# transmitter_new.net
KiCad netlist of a schematic drawn in EAGLE
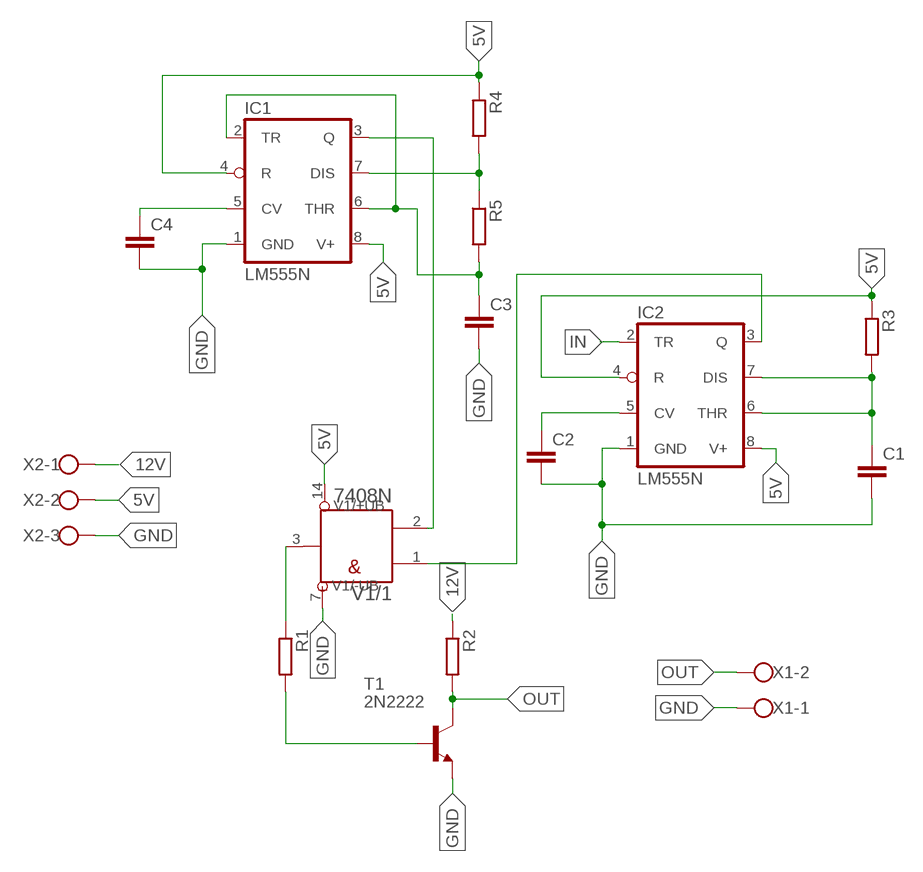
[diagram p0: schematic, sheet 1]

(export (version "E")
  (design (tool "Eeschema 10.0.6"))
  (components
    (comp (ref "C1")
      (value "C-EU050-025X075")
      (footprint "eagle-import:C050-025X075")
      (libsource (lib "eagle-import") (part "C-EU050-025X075"))
    )
    (comp (ref "C2")
      (value "C-EU050-025X075")
      (footprint "eagle-import:C050-025X075")
      (libsource (lib "eagle-import") (part "C-EU050-025X075"))
    )
    (comp (ref "C3")
      (value "C-EU050-025X075")
      (footprint "eagle-import:C050-025X075")
      (libsource (lib "eagle-import") (part "C-EU050-025X075"))
    )
    (comp (ref "C4")
      (value "C-EU050-025X075")
      (footprint "eagle-import:C050-025X075")
      (libsource (lib "eagle-import") (part "C-EU050-025X075"))
    )
    (comp (ref "IC1")
      (value "LM555N")
      (footprint "eagle-import:DIL08")
      (libsource (lib "eagle-import") (part "555NLM"))
    )
    (comp (ref "IC2")
      (value "LM555N")
      (footprint "eagle-import:DIL08")
      (libsource (lib "eagle-import") (part "555NLM"))
    )
    (comp (ref "R1")
      (value "R-EU_0207/10")
      (footprint "eagle-import:0207_10")
      (libsource (lib "eagle-import") (part "R-EU_0207/10"))
    )
    (comp (ref "R2")
      (value "R-EU_0207/10")
      (footprint "eagle-import:0207_10")
      (libsource (lib "eagle-import") (part "R-EU_0207/10"))
    )
    (comp (ref "R3")
      (value "R-EU_0207/10")
      (footprint "eagle-import:0207_10")
      (libsource (lib "eagle-import") (part "R-EU_0207/10"))
    )
    (comp (ref "R4")
      (value "R-EU_0207/10")
      (footprint "eagle-import:0207_10")
      (libsource (lib "eagle-import") (part "R-EU_0207/10"))
    )
    (comp (ref "R5")
      (value "R-EU_0207/10")
      (footprint "eagle-import:0207_10")
      (libsource (lib "eagle-import") (part "R-EU_0207/10"))
    )
    (comp (ref "T1")
      (value "2N2222")
      (footprint "eagle-import:TO18")
      (libsource (lib "eagle-import") (part "2N2222"))
    )
    (comp (ref "V1")
      (value "7408N")
      (footprint "eagle-import:DIL14")
      (libsource (lib "eagle-import") (part "7408N"))
    )
    (comp (ref "X1")
      (value "W237-102")
      (footprint "eagle-import:W237-102")
      (fields (field (name "MPN") "237-102"))
      (libsource (lib "eagle-import") (part "W237-102"))
    )
    (comp (ref "X2")
      (value "W237-103")
      (footprint "eagle-import:W237-103")
      (fields (field (name "MPN") "237-103"))
      (libsource (lib "eagle-import") (part "W237-103"))
    )
  )
  (nets
    (net (code "1") (name "5V") (class "Default")
      (node (ref "IC1") (pin "4") (pinfunction "R_4") (pintype "input"))
      (node (ref "IC1") (pin "8") (pinfunction "V+_8") (pintype "power_in"))
      (node (ref "IC2") (pin "4") (pinfunction "R_4") (pintype "input"))
      (node (ref "IC2") (pin "8") (pinfunction "V+_8") (pintype "power_in"))
      (node (ref "R3") (pin "1") (pinfunction "1_1") (pintype "passive"))
      (node (ref "R4") (pin "1") (pinfunction "1_1") (pintype "passive"))
      (node (ref "V1") (pin "14") (pinfunction "+UB_14") (pintype "power_in"))
      (node (ref "X2") (pin "2") (pinfunction "KL_2") (pintype "passive"))
    )
    (net (code "2") (name "12V") (class "Default")
      (node (ref "R2") (pin "1") (pinfunction "1_1") (pintype "passive"))
      (node (ref "X2") (pin "1") (pinfunction "KL_1") (pintype "passive"))
    )
    (net (code "3") (name "GND") (class "Default")
      (node (ref "C1") (pin "2") (pinfunction "2_2") (pintype "passive"))
      (node (ref "C2") (pin "2") (pinfunction "2_2") (pintype "passive"))
      (node (ref "C3") (pin "2") (pinfunction "2_2") (pintype "passive"))
      (node (ref "C4") (pin "2") (pinfunction "2_2") (pintype "passive"))
      (node (ref "IC1") (pin "1") (pinfunction "GND_1") (pintype "power_in"))
      (node (ref "IC2") (pin "1") (pinfunction "GND_1") (pintype "power_in"))
      (node (ref "T1") (pin "1") (pinfunction "E_1") (pintype "passive"))
      (node (ref "V1") (pin "7") (pinfunction "-UB_7") (pintype "power_in"))
      (node (ref "X1") (pin "1") (pinfunction "KL_1") (pintype "passive"))
      (node (ref "X2") (pin "3") (pinfunction "KL_3") (pintype "passive"))
    )
    (net (code "4") (name "IN") (class "Default")
      (node (ref "IC2") (pin "2") (pinfunction "TR_2") (pintype "input"))
    )
    (net (code "5") (name "Net-(IC1-CV)") (class "Default")
      (node (ref "C4") (pin "1") (pinfunction "1_1") (pintype "passive"))
      (node (ref "IC1") (pin "5") (pinfunction "CV_5") (pintype "input"))
    )
    (net (code "6") (name "Net-(IC1-DIS)") (class "Default")
      (node (ref "IC1") (pin "7") (pinfunction "DIS_7") (pintype "input"))
      (node (ref "R4") (pin "2") (pinfunction "2_2") (pintype "passive"))
      (node (ref "R5") (pin "1") (pinfunction "1_1") (pintype "passive"))
    )
    (net (code "7") (name "Net-(IC1-Q)") (class "Default")
      (node (ref "IC1") (pin "3") (pinfunction "Q_3") (pintype "output"))
      (node (ref "V1") (pin "2") (pinfunction "B_2") (pintype "input"))
    )
    (net (code "8") (name "Net-(IC1-THR)") (class "Default")
      (node (ref "C3") (pin "1") (pinfunction "1_1") (pintype "passive"))
      (node (ref "IC1") (pin "2") (pinfunction "TR_2") (pintype "input"))
      (node (ref "IC1") (pin "6") (pinfunction "THR_6") (pintype "input"))
      (node (ref "R5") (pin "2") (pinfunction "2_2") (pintype "passive"))
    )
    (net (code "9") (name "Net-(IC2-CV)") (class "Default")
      (node (ref "C2") (pin "1") (pinfunction "1_1") (pintype "passive"))
      (node (ref "IC2") (pin "5") (pinfunction "CV_5") (pintype "input"))
    )
    (net (code "10") (name "Net-(IC2-DIS)") (class "Default")
      (node (ref "C1") (pin "1") (pinfunction "1_1") (pintype "passive"))
      (node (ref "IC2") (pin "6") (pinfunction "THR_6") (pintype "input"))
      (node (ref "IC2") (pin "7") (pinfunction "DIS_7") (pintype "input"))
      (node (ref "R3") (pin "2") (pinfunction "2_2") (pintype "passive"))
    )
    (net (code "11") (name "Net-(IC2-Q)") (class "Default")
      (node (ref "IC2") (pin "3") (pinfunction "Q_3") (pintype "output"))
      (node (ref "V1") (pin "1") (pinfunction "A_1") (pintype "input"))
    )
    (net (code "12") (name "Net-(T1-B)") (class "Default")
      (node (ref "R1") (pin "2") (pinfunction "2_2") (pintype "passive"))
      (node (ref "T1") (pin "2") (pinfunction "B_2") (pintype "passive"))
    )
    (net (code "13") (name "Net-(V1C-Y)") (class "Default")
      (node (ref "R1") (pin "1") (pinfunction "1_1") (pintype "passive"))
      (node (ref "V1") (pin "3") (pinfunction "Y_3") (pintype "output"))
    )
    (net (code "14") (name "OUT") (class "Default")
      (node (ref "R2") (pin "2") (pinfunction "2_2") (pintype "passive"))
      (node (ref "T1") (pin "3") (pinfunction "C_3") (pintype "passive"))
      (node (ref "X1") (pin "2") (pinfunction "KL_2") (pintype "passive"))
    )
  )
)
